# touch.net
KiCad netlist of a schematic drawn in EAGLE
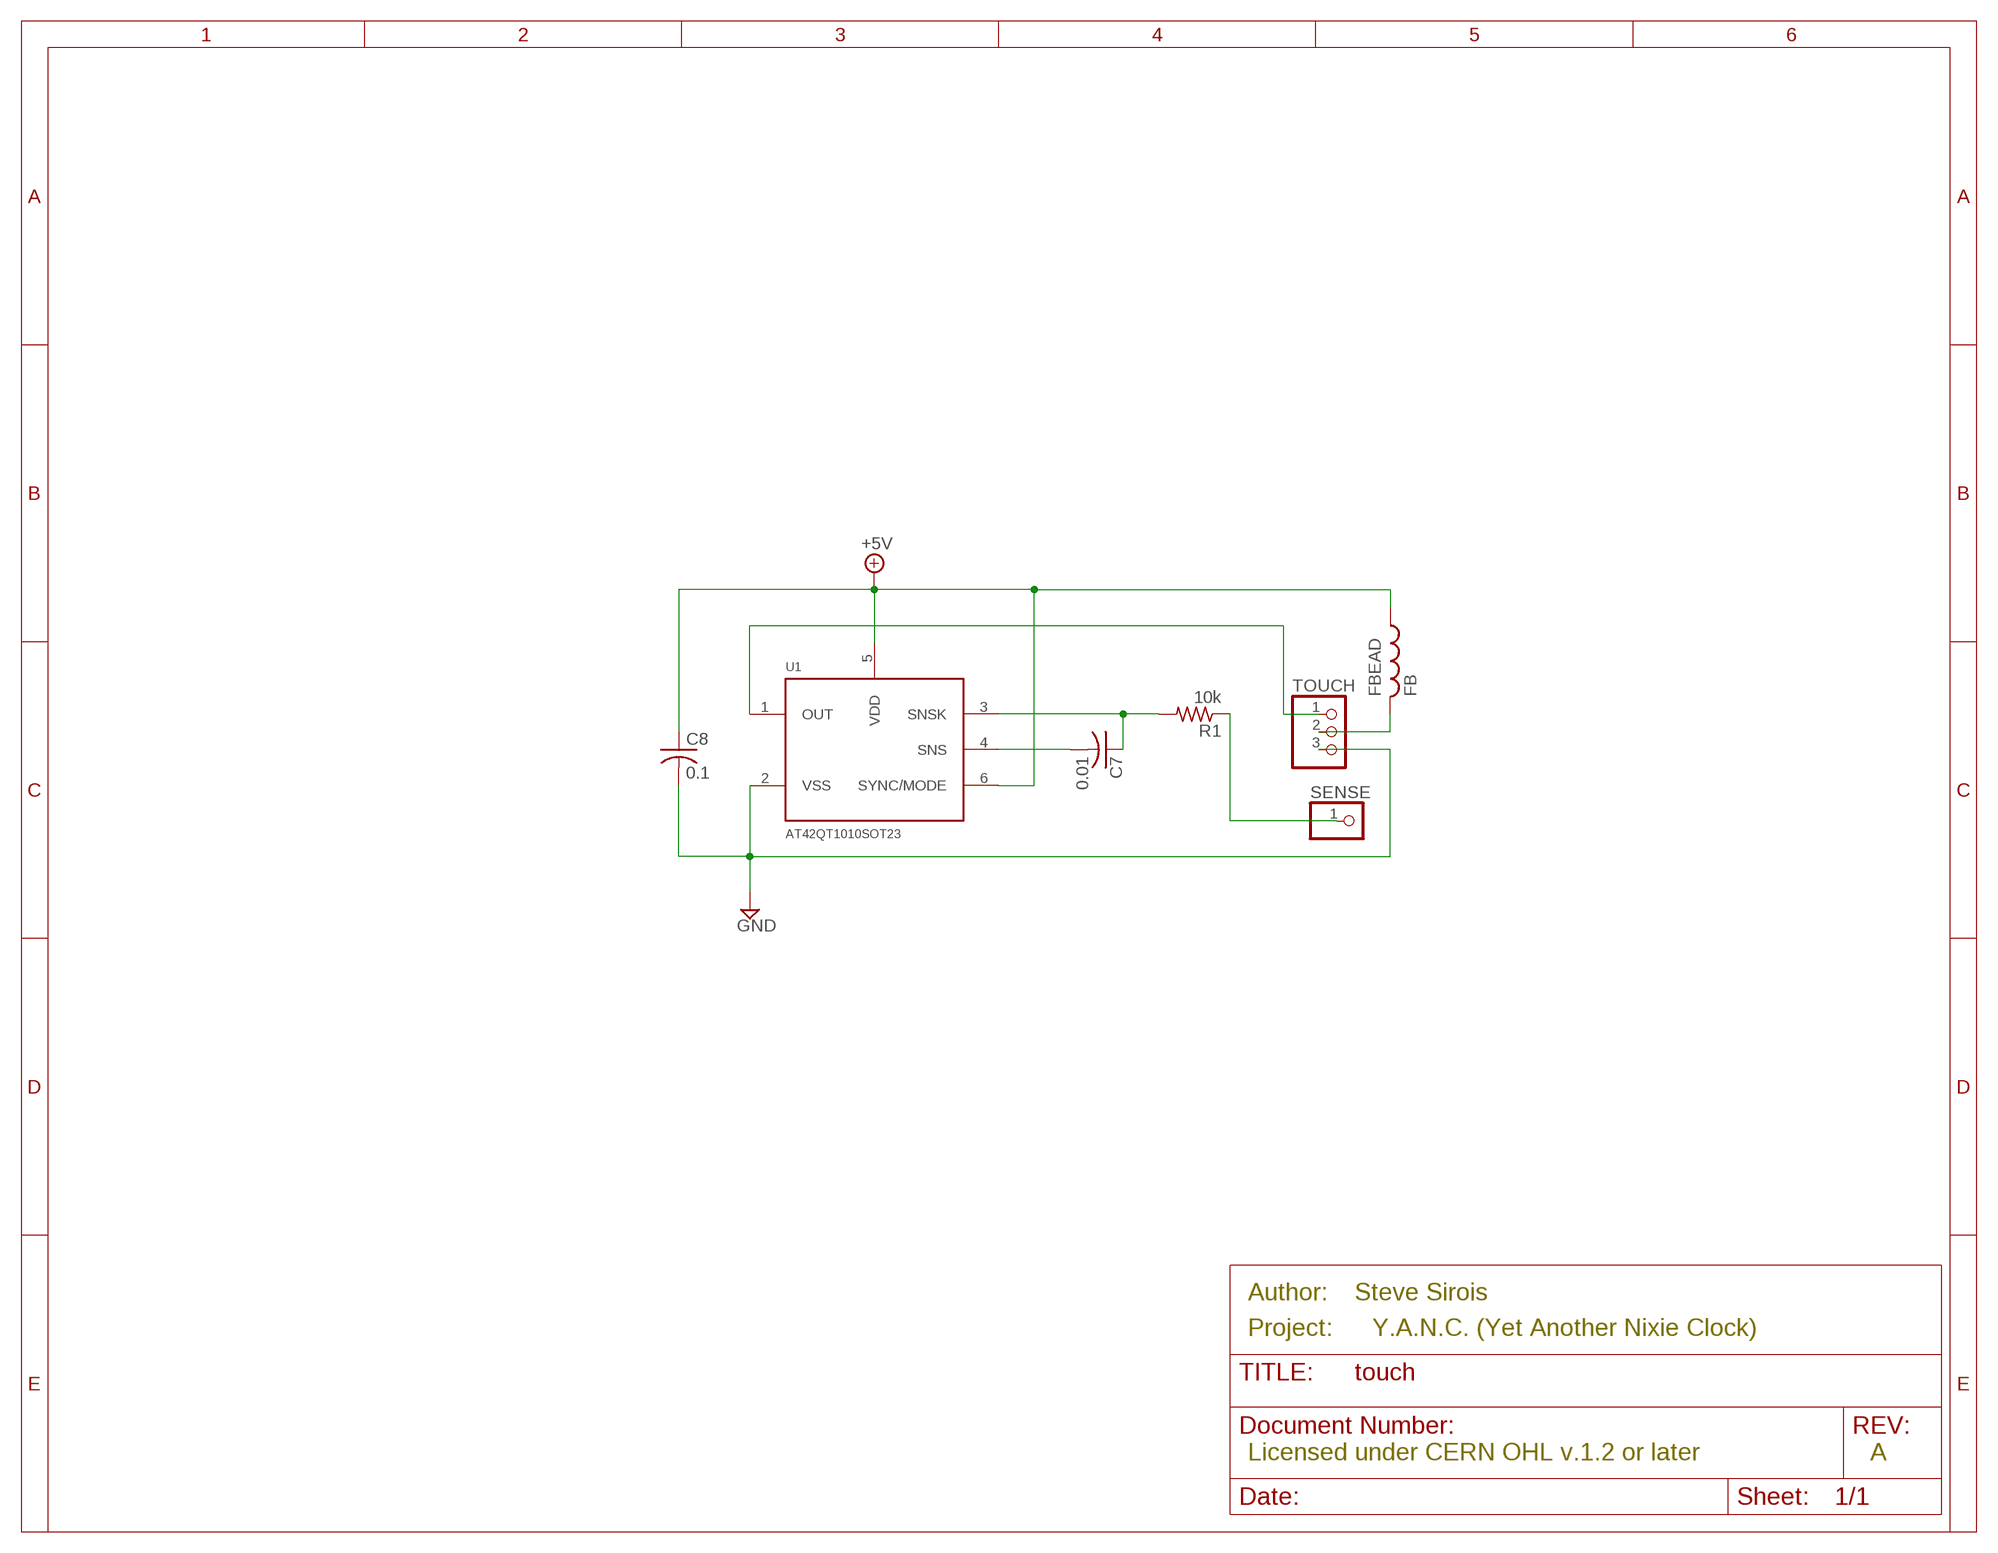
[diagram p0: schematic, sheet 1]

(export (version "E")
  (design (tool "Eeschema 10.0.6"))
  (components
    (comp (ref "C7")
      (value "0.01")
      (footprint "eagle-import:C025-025X050")
      (libsource (lib "eagle-import") (part "C-US025-025X050"))
    )
    (comp (ref "C8")
      (value "0.1")
      (footprint "eagle-import:C025-025X050")
      (libsource (lib "eagle-import") (part "C-US025-025X050"))
    )
    (comp (ref "FBEAD")
      (value "FB")
      (footprint "eagle-import:FB")
      (libsource (lib "eagle-import") (part "FB"))
    )
    (comp (ref "R1")
      (value "10k")
      (footprint "eagle-import:0207_10")
      (libsource (lib "eagle-import") (part "R-US_0207/10"))
    )
    (comp (ref "SENSE")
      (value "PINHD-1X1")
      (footprint "eagle-import:1X01")
      (libsource (lib "eagle-import") (part "PINHD-1X1"))
    )
    (comp (ref "TOUCH")
      (value "PINHD-1X3")
      (footprint "eagle-import:1X03")
      (libsource (lib "eagle-import") (part "PINHD-1X3"))
    )
    (comp (ref "U1")
      (value "AT42QT1010SOT23")
      (footprint "eagle-import:SOT23-6")
      (libsource (lib "eagle-import") (part "AT42QT1010SOT23"))
    )
  )
  (nets
    (net (code "1") (name "+5V") (class "Default")
      (node (ref "C8") (pin "1") (pinfunction "1_1") (pintype "passive"))
      (node (ref "FBEAD") (pin "P$1") (pinfunction "1_P$1") (pintype "passive"))
      (node (ref "U1") (pin "5") (pinfunction "VDD_5") (pintype "bidirectional"))
      (node (ref "U1") (pin "6") (pinfunction "SYNC/MODE_6") (pintype "bidirectional"))
    )
    (net (code "2") (name "GND") (class "Default")
      (node (ref "C8") (pin "2") (pinfunction "2_2") (pintype "passive"))
      (node (ref "TOUCH") (pin "3") (pinfunction "3_3") (pintype "passive"))
      (node (ref "U1") (pin "2") (pinfunction "VSS_2") (pintype "bidirectional"))
    )
    (net (code "3") (name "Net-(FBEAD-2)") (class "Default")
      (node (ref "FBEAD") (pin "P$2") (pinfunction "2_P$2") (pintype "passive"))
      (node (ref "TOUCH") (pin "2") (pinfunction "2_2") (pintype "passive"))
    )
    (net (code "4") (name "Net-(R1-Pad1)") (class "Default")
      (node (ref "R1") (pin "1") (pinfunction "1_1") (pintype "passive"))
      (node (ref "SENSE") (pin "1") (pinfunction "1_1") (pintype "passive"))
    )
    (net (code "5") (name "Net-(U1-OUT)") (class "Default")
      (node (ref "TOUCH") (pin "1") (pinfunction "1_1") (pintype "passive"))
      (node (ref "U1") (pin "1") (pinfunction "OUT_1") (pintype "bidirectional"))
    )
    (net (code "6") (name "Net-(U1-SNS)") (class "Default")
      (node (ref "C7") (pin "2") (pinfunction "2_2") (pintype "passive"))
      (node (ref "U1") (pin "4") (pinfunction "SNS_4") (pintype "bidirectional"))
    )
    (net (code "7") (name "Net-(U1-SNSK)") (class "Default")
      (node (ref "C7") (pin "1") (pinfunction "1_1") (pintype "passive"))
      (node (ref "R1") (pin "2") (pinfunction "2_2") (pintype "passive"))
      (node (ref "U1") (pin "3") (pinfunction "SNSK_3") (pintype "bidirectional"))
    )
  )
)
